# pmu.net
KiCad netlist of a schematic drawn in Altium Designer
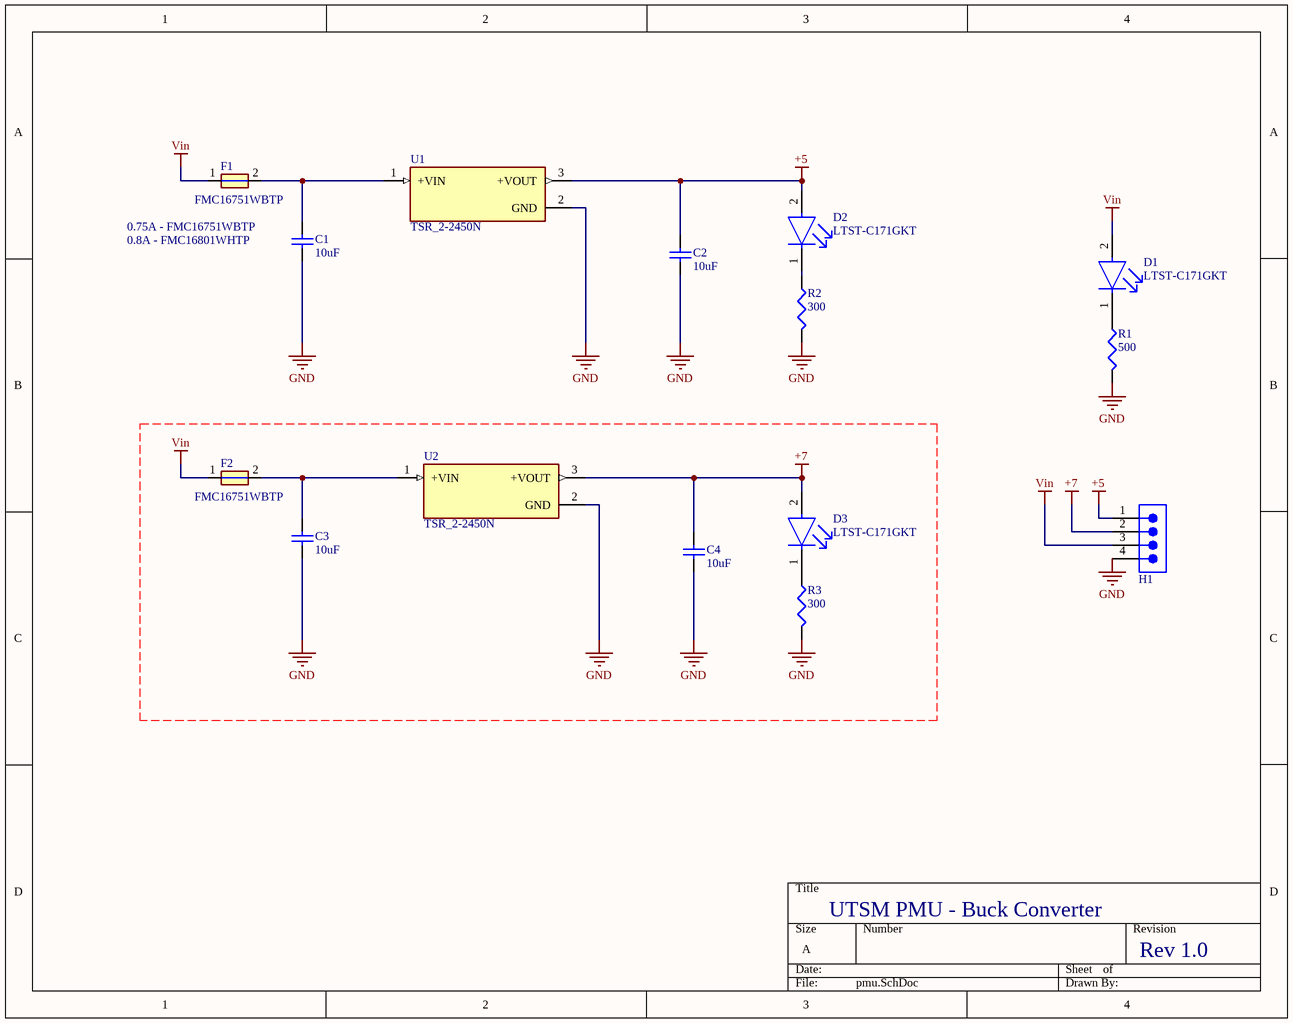
[diagram p0: pmu.SchDoc]

(export (version "E")
  (design (tool "Eeschema 10.0.6"))
  (components
    (comp (ref "C1")
      (value "10uF")
      (footprint "0603c")
      (description "SMD Capacitor\r\nCL21A106KOQNNNG")
      (fields (field (name "Comment") "Cap") (field (name "PUBLISHER") "Altium Limited"))
      (libsource (lib "pmu") (part "Cap"))
    )
    (comp (ref "C2")
      (value "10uF")
      (footprint "0603c")
      (description "SMD Capacitor")
      (fields (field (name "Comment") "Cap") (field (name "PUBLISHER") "Altium Limited"))
      (libsource (lib "pmu") (part "Cap"))
    )
    (comp (ref "C3")
      (value "10uF")
      (footprint "0603c")
      (description "SMD Capacitor\r\nCL21A106KOQNNNG")
      (fields (field (name "Comment") "Cap") (field (name "PUBLISHER") "Altium Limited"))
      (libsource (lib "pmu") (part "Cap"))
    )
    (comp (ref "C4")
      (value "10uF")
      (footprint "0603c")
      (description "SMD Capacitor")
      (fields (field (name "Comment") "Cap") (field (name "PUBLISHER") "Altium Limited"))
      (libsource (lib "pmu") (part "Cap"))
    )
    (comp (ref "D1")
      (value "LTST-C171GKT")
      (footprint "FP-LTST-C171GKT-MFG")
      (description "LED GREEN CLEAR CHIP SMD")
      (libsource (lib "Altium Content Vault") (part "8706943c75ba83719d021d2fdc84c58"))
    )
    (comp (ref "D2")
      (value "LTST-C171GKT")
      (footprint "FP-LTST-C171GKT-MFG")
      (description "LED GREEN CLEAR CHIP SMD")
      (libsource (lib "Altium Content Vault") (part "8706943c75ba83719d021d2fdc84c58"))
    )
    (comp (ref "D3")
      (value "LTST-C171GKT")
      (footprint "FP-LTST-C171GKT-MFG")
      (description "LED GREEN CLEAR CHIP SMD")
      (libsource (lib "Altium Content Vault") (part "8706943c75ba83719d021d2fdc84c58"))
    )
    (comp (ref "F1")
      (value "FMC16751WBTP")
      (footprint "FUSC1608X64N")
      (description "0.8A - FMC16801WHTP\r\n0.75A - FMC16751WBTP")
      (fields (field (name "MP") "ERB-RE1R00V") (field (name "MF") "Panasonic"))
      (libsource (lib "pmu") (part "ERB-RE1R00V"))
    )
    (comp (ref "F2")
      (value "FMC16751WBTP")
      (footprint "FUSC1608X64N")
      (description "0.8A - FMC16801WHTP\r\n0.75A - FMC16751WBTP")
      (fields (field (name "MP") "ERB-RE1R00V") (field (name "MF") "Panasonic"))
      (libsource (lib "pmu") (part "ERB-RE1R00V"))
    )
    (comp (ref "H1")
      (value "61300411121")
      (footprint "61300411121")
      (description "WR-PHD Pin Header, THT, Vertical, pitch 2.54mm, 1 Row, 4P")
      (fields (field (name "MANUFACTURER") "Wurth Elektronik"))
      (libsource (lib "pmu") (part "61300411121"))
    )
    (comp (ref "R1")
      (value "500")
      (footprint "0603r")
      (description "SMD Resistor")
      (fields (field (name "PUBLISHER") "Altium Limited"))
      (libsource (lib "pmu") (part "Res3"))
    )
    (comp (ref "R2")
      (value "300")
      (footprint "0603r")
      (description "SMD Resistor")
      (fields (field (name "PUBLISHER") "Altium Limited"))
      (libsource (lib "pmu") (part "Res3"))
    )
    (comp (ref "R3")
      (value "300")
      (footprint "0603r")
      (description "SMD Resistor")
      (fields (field (name "PUBLISHER") "Altium Limited"))
      (libsource (lib "pmu") (part "Res3"))
    )
    (comp (ref "U1")
      (value "TSR_2-2450N")
      (footprint "CONV_TSR_2-2450N")
      (fields (field (name "MF") "{'manufacturer': u'Traco Power'}"))
      (libsource (lib "pmu") (part "TSR_2-2450N"))
    )
    (comp (ref "U2")
      (value "TSR_2-2450N")
      (footprint "CONV_TSR_2-2450N")
      (fields (field (name "MF") "{'manufacturer': u'Traco Power'}"))
      (libsource (lib "pmu") (part "TSR_2-2450N"))
    )
  )
  (nets
    (net (code "1") (name "+5") (class "Default")
      (node (ref "C2") (pin "2") (pinfunction "2_2") (pintype "passive"))
      (node (ref "D2") (pin "2") (pinfunction "A_2") (pintype "passive"))
      (node (ref "H1") (pin "1") (pinfunction "1_1") (pintype "passive"))
      (node (ref "U1") (pin "3") (pinfunction "+VOUT_3") (pintype "output"))
    )
    (net (code "2") (name "+7") (class "Default")
      (node (ref "C4") (pin "2") (pinfunction "2_2") (pintype "passive"))
      (node (ref "D3") (pin "2") (pinfunction "A_2") (pintype "passive"))
      (node (ref "H1") (pin "2") (pinfunction "2_2") (pintype "passive"))
      (node (ref "U2") (pin "3") (pinfunction "+VOUT_3") (pintype "output"))
    )
    (net (code "3") (name "GND") (class "Default")
      (node (ref "C1") (pin "1") (pinfunction "1_1") (pintype "passive"))
      (node (ref "C2") (pin "1") (pinfunction "1_1") (pintype "passive"))
      (node (ref "C3") (pin "1") (pinfunction "1_1") (pintype "passive"))
      (node (ref "C4") (pin "1") (pinfunction "1_1") (pintype "passive"))
      (node (ref "H1") (pin "4") (pinfunction "4_4") (pintype "passive"))
      (node (ref "R1") (pin "2") (pinfunction "2_2") (pintype "passive"))
      (node (ref "R2") (pin "2") (pinfunction "2_2") (pintype "passive"))
      (node (ref "R3") (pin "2") (pinfunction "2_2") (pintype "passive"))
      (node (ref "U1") (pin "2") (pinfunction "GND_2") (pintype "power_in"))
      (node (ref "U2") (pin "2") (pinfunction "GND_2") (pintype "power_in"))
    )
    (net (code "4") (name "Net-(D1-C)") (class "Default")
      (node (ref "D1") (pin "1") (pinfunction "C_1") (pintype "passive"))
      (node (ref "R1") (pin "1") (pinfunction "1_1") (pintype "passive"))
    )
    (net (code "5") (name "Net-(D2-C)") (class "Default")
      (node (ref "D2") (pin "1") (pinfunction "C_1") (pintype "passive"))
      (node (ref "R2") (pin "1") (pinfunction "1_1") (pintype "passive"))
    )
    (net (code "6") (name "Net-(D3-C)") (class "Default")
      (node (ref "D3") (pin "1") (pinfunction "C_1") (pintype "passive"))
      (node (ref "R3") (pin "1") (pinfunction "1_1") (pintype "passive"))
    )
    (net (code "7") (name "Net-(U1-+VIN)") (class "Default")
      (node (ref "C1") (pin "2") (pinfunction "2_2") (pintype "passive"))
      (node (ref "F1") (pin "2") (pinfunction "2_2") (pintype "passive"))
      (node (ref "U1") (pin "1") (pinfunction "+VIN_1") (pintype "input"))
    )
    (net (code "8") (name "Net-(U2-+VIN)") (class "Default")
      (node (ref "C3") (pin "2") (pinfunction "2_2") (pintype "passive"))
      (node (ref "F2") (pin "2") (pinfunction "2_2") (pintype "passive"))
      (node (ref "U2") (pin "1") (pinfunction "+VIN_1") (pintype "input"))
    )
    (net (code "9") (name "Vin") (class "Default")
      (node (ref "D1") (pin "2") (pinfunction "A_2") (pintype "passive"))
      (node (ref "F1") (pin "1") (pinfunction "1_1") (pintype "passive"))
      (node (ref "F2") (pin "1") (pinfunction "1_1") (pintype "passive"))
      (node (ref "H1") (pin "3") (pinfunction "3_3") (pintype "passive"))
    )
  )
)
